# ESP32.net
KiCad netlist of a schematic drawn in Altium Designer
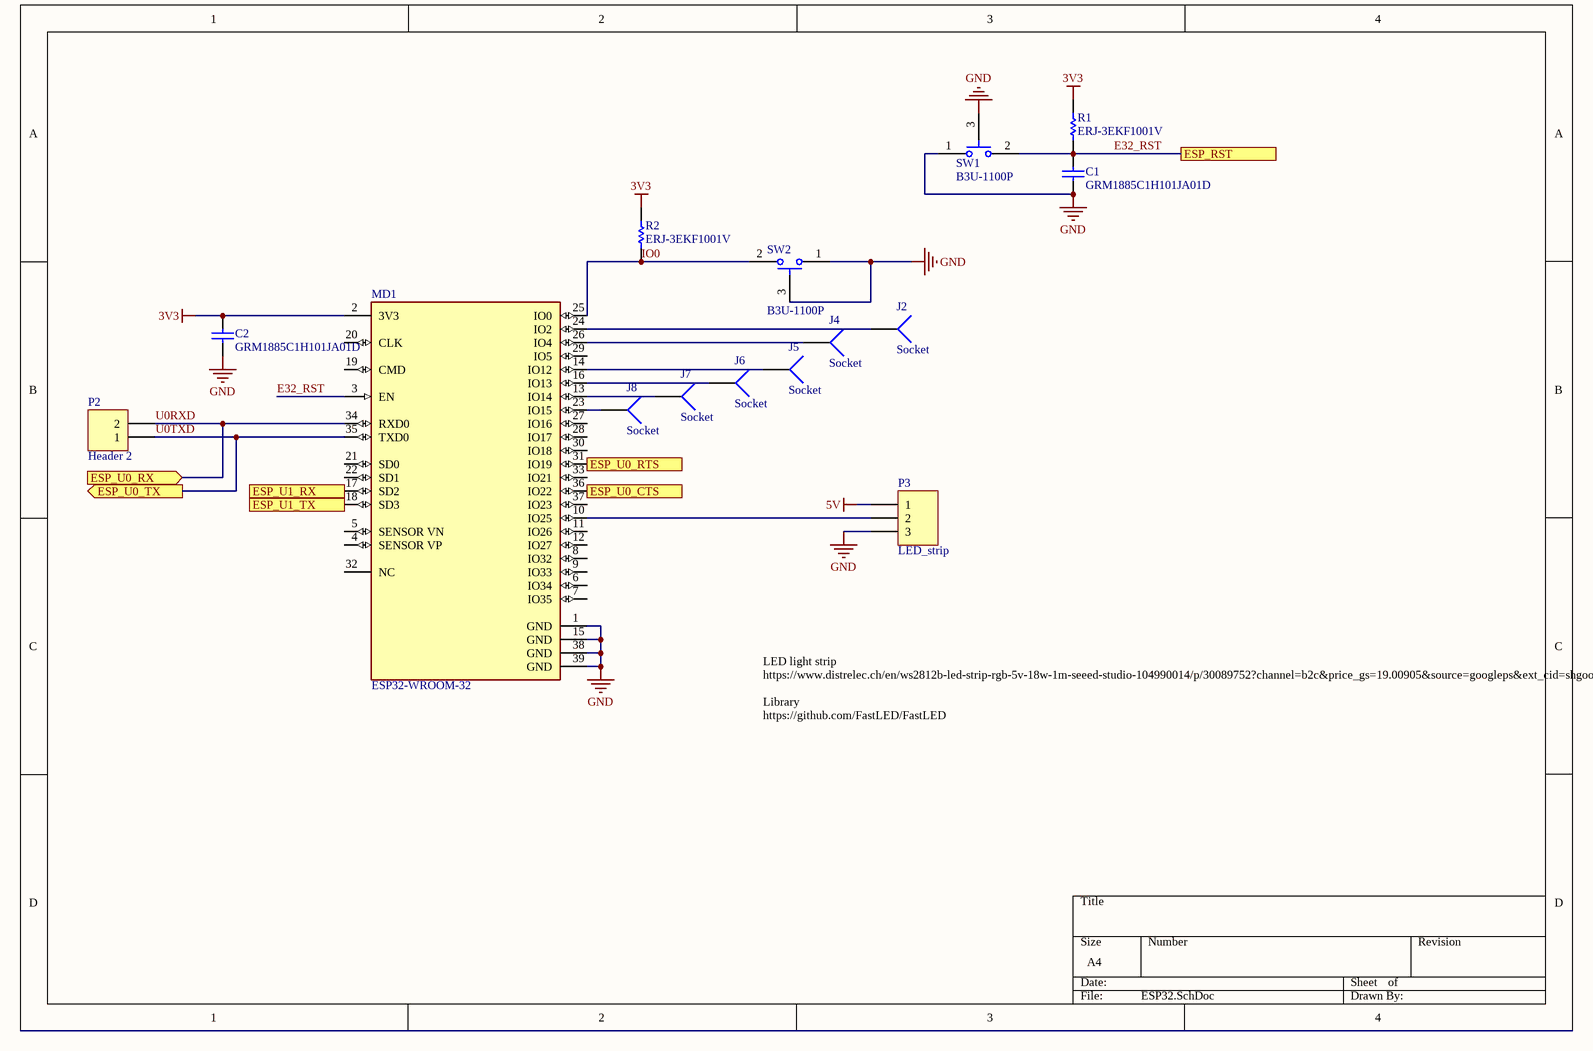
[diagram p0: ESP32.SchDoc]

(export (version "E")
  (design (tool "Eeschema 10.0.6"))
  (components
    (comp (ref "C1")
      (value "GRM1885C1H101JA01D")
      (footprint "CAPC1608X90X35ML10T15")
      (fields (field (name "MANUFACTURER") "Murata"))
      (libsource (lib "Altium Content Vault") (part "CAP"))
    )
    (comp (ref "C2")
      (value "GRM1885C1H101JA01D")
      (footprint "CAPC1608X90X35ML10T15")
      (fields (field (name "MANUFACTURER") "Murata"))
      (libsource (lib "Altium Content Vault") (part "CAP"))
    )
    (comp (ref "J2")
      (value "Socket")
      (footprint "PIN1")
      (fields (field (name "PUBLISHER") "Altium Limited"))
      (libsource (lib "Miscellaneous Connectors") (part "Socket"))
    )
    (comp (ref "J4")
      (value "Socket")
      (footprint "PIN1")
      (fields (field (name "PUBLISHER") "Altium Limited"))
      (libsource (lib "Miscellaneous Connectors") (part "Socket"))
    )
    (comp (ref "J5")
      (value "Socket")
      (footprint "PIN1")
      (fields (field (name "PUBLISHER") "Altium Limited"))
      (libsource (lib "Miscellaneous Connectors") (part "Socket"))
    )
    (comp (ref "J6")
      (value "Socket")
      (footprint "PIN1")
      (fields (field (name "PUBLISHER") "Altium Limited"))
      (libsource (lib "Miscellaneous Connectors") (part "Socket"))
    )
    (comp (ref "J7")
      (value "Socket")
      (footprint "PIN1")
      (fields (field (name "PUBLISHER") "Altium Limited"))
      (libsource (lib "Miscellaneous Connectors") (part "Socket"))
    )
    (comp (ref "J8")
      (value "Socket")
      (footprint "PIN1")
      (fields (field (name "PUBLISHER") "Altium Limited"))
      (libsource (lib "Miscellaneous Connectors") (part "Socket"))
    )
    (comp (ref "MD1")
      (value "ESP32-WROOM-32")
      (footprint "FP-ESP32-WROOM-32-MFG")
      (description "RX TXRX MOD WIFI SURFACE MOUNT")
      (libsource (lib "Altium Content Vault") (part "ee866abf0b6c51247b7f5cdebf2f250"))
    )
    (comp (ref "P2")
      (value "Header 2")
      (footprint "HDR1X2")
      (description "Header, 2-Pin")
      (fields (field (name "PUBLISHER") "Altium Limited"))
      (libsource (lib "Miscellaneous Connectors") (part "Header 2"))
    )
    (comp (ref "P3")
      (value "LED_strip")
      (footprint "HDR1X3")
      (description "Header, 3-Pin")
      (fields (field (name "PUBLISHER") "Altium Limited"))
      (libsource (lib "Miscellaneous Connectors") (part "Header 3"))
    )
    (comp (ref "R1")
      (value "ERJ-3EKF1001V")
      (footprint "RESC1608X55X30ML15T15")
      (fields (field (name "MANUFACTURER") "Panasonic"))
      (libsource (lib "Altium Content Vault") (part "RES"))
    )
    (comp (ref "R2")
      (value "ERJ-3EKF1001V")
      (footprint "RESC1608X55X30ML15T15")
      (fields (field (name "MANUFACTURER") "Panasonic"))
      (libsource (lib "Altium Content Vault") (part "RES"))
    )
    (comp (ref "SW1")
      (value "B3U-1100P")
      (footprint "FP-B3U-1100P-MFG")
      (description "SWITCH TACTILE SPST-NO 0.05A 12V")
      (libsource (lib "Altium Content Vault") (part "7997d68e903f5bf27f0182c444d3d80"))
    )
    (comp (ref "SW2")
      (value "B3U-1100P")
      (footprint "FP-B3U-1100P-MFG")
      (description "SWITCH TACTILE SPST-NO 0.05A 12V")
      (libsource (lib "Altium Content Vault") (part "7997d68e903f5bf27f0182c444d3d80"))
    )
  )
  (nets
    (net (code "1") (name "/E32_RST") (class "Default")
      (node (ref "C1") (pin "2") (pinfunction "2_2") (pintype "passive"))
      (node (ref "MD1") (pin "3") (pinfunction "EN_3") (pintype "input"))
      (node (ref "R1") (pin "1") (pinfunction "1_1") (pintype "passive"))
      (node (ref "SW1") (pin "2") (pinfunction "2_2") (pintype "passive"))
    )
    (net (code "2") (name "/ESP_U0_CTS") (class "Default")
      (node (ref "MD1") (pin "36") (pinfunction "IO22_36") (pintype "bidirectional"))
    )
    (net (code "3") (name "/ESP_U0_RTS") (class "Default")
      (node (ref "MD1") (pin "31") (pinfunction "IO19_31") (pintype "bidirectional"))
    )
    (net (code "4") (name "/ESP_U1_RX") (class "Default")
      (node (ref "MD1") (pin "17") (pinfunction "SD2_17") (pintype "bidirectional"))
    )
    (net (code "5") (name "/ESP_U1_TX") (class "Default")
      (node (ref "MD1") (pin "18") (pinfunction "SD3_18") (pintype "bidirectional"))
    )
    (net (code "6") (name "/IO0") (class "Default")
      (node (ref "MD1") (pin "25") (pinfunction "IO0_25") (pintype "bidirectional"))
      (node (ref "R2") (pin "1") (pinfunction "1_1") (pintype "passive"))
      (node (ref "SW2") (pin "2") (pinfunction "2_2") (pintype "passive"))
    )
    (net (code "7") (name "/U0RXD") (class "Default")
      (node (ref "MD1") (pin "34") (pinfunction "RXD0_34") (pintype "bidirectional"))
      (node (ref "P2") (pin "2") (pinfunction "2_2") (pintype "passive"))
    )
    (net (code "8") (name "/U0TXD") (class "Default")
      (node (ref "MD1") (pin "35") (pinfunction "TXD0_35") (pintype "bidirectional"))
      (node (ref "P2") (pin "1") (pinfunction "1_1") (pintype "passive"))
    )
    (net (code "9") (name "3V3") (class "Default")
      (node (ref "C2") (pin "2") (pinfunction "2_2") (pintype "passive"))
      (node (ref "MD1") (pin "2") (pinfunction "3V3_2") (pintype "power_in"))
      (node (ref "R1") (pin "2") (pinfunction "2_2") (pintype "passive"))
      (node (ref "R2") (pin "2") (pinfunction "2_2") (pintype "passive"))
    )
    (net (code "10") (name "5V") (class "Default")
      (node (ref "P3") (pin "1") (pinfunction "1_1") (pintype "passive"))
    )
    (net (code "11") (name "GND") (class "Default")
      (node (ref "C1") (pin "1") (pinfunction "1_1") (pintype "passive"))
      (node (ref "C2") (pin "1") (pinfunction "1_1") (pintype "passive"))
      (node (ref "MD1") (pin "1") (pinfunction "GND_1") (pintype "power_in"))
      (node (ref "MD1") (pin "15") (pinfunction "GND_15") (pintype "power_in"))
      (node (ref "MD1") (pin "38") (pinfunction "GND_38") (pintype "power_in"))
      (node (ref "MD1") (pin "39") (pinfunction "GND_39") (pintype "power_in"))
      (node (ref "P3") (pin "3") (pinfunction "3_3") (pintype "passive"))
      (node (ref "SW1") (pin "1") (pinfunction "1_1") (pintype "passive"))
      (node (ref "SW1") (pin "3") (pinfunction "3_3") (pintype "passive"))
      (node (ref "SW2") (pin "1") (pinfunction "1_1") (pintype "passive"))
      (node (ref "SW2") (pin "3") (pinfunction "3_3") (pintype "passive"))
    )
    (net (code "12") (name "Net-(MD1-IO2)") (class "Default")
      (node (ref "J2") (pin "1") (pinfunction "1_1") (pintype "passive"))
      (node (ref "MD1") (pin "24") (pinfunction "IO2_24") (pintype "bidirectional"))
    )
    (net (code "13") (name "Net-(MD1-IO4)") (class "Default")
      (node (ref "J4") (pin "1") (pinfunction "1_1") (pintype "passive"))
      (node (ref "MD1") (pin "26") (pinfunction "IO4_26") (pintype "bidirectional"))
    )
    (net (code "14") (name "Net-(MD1-IO12)") (class "Default")
      (node (ref "J5") (pin "1") (pinfunction "1_1") (pintype "passive"))
      (node (ref "MD1") (pin "14") (pinfunction "IO12_14") (pintype "bidirectional"))
    )
    (net (code "15") (name "Net-(MD1-IO13)") (class "Default")
      (node (ref "J6") (pin "1") (pinfunction "1_1") (pintype "passive"))
      (node (ref "MD1") (pin "16") (pinfunction "IO13_16") (pintype "bidirectional"))
    )
    (net (code "16") (name "Net-(MD1-IO14)") (class "Default")
      (node (ref "J7") (pin "1") (pinfunction "1_1") (pintype "passive"))
      (node (ref "MD1") (pin "13") (pinfunction "IO14_13") (pintype "bidirectional"))
    )
    (net (code "17") (name "Net-(MD1-IO15)") (class "Default")
      (node (ref "J8") (pin "1") (pinfunction "1_1") (pintype "passive"))
      (node (ref "MD1") (pin "23") (pinfunction "IO15_23") (pintype "bidirectional"))
    )
    (net (code "18") (name "Net-(MD1-IO25)") (class "Default")
      (node (ref "MD1") (pin "10") (pinfunction "IO25_10") (pintype "bidirectional"))
      (node (ref "P3") (pin "2") (pinfunction "2_2") (pintype "passive"))
    )
    (net (code "19") (name "unconnected-(MD1-CLK-Pad20)") (class "Default")
      (node (ref "MD1") (pin "20") (pinfunction "CLK_20") (pintype "bidirectional"))
    )
    (net (code "20") (name "unconnected-(MD1-CMD-Pad19)") (class "Default")
      (node (ref "MD1") (pin "19") (pinfunction "CMD_19") (pintype "bidirectional"))
    )
    (net (code "21") (name "unconnected-(MD1-IO5-Pad29)") (class "Default")
      (node (ref "MD1") (pin "29") (pinfunction "IO5_29") (pintype "bidirectional"))
    )
    (net (code "22") (name "unconnected-(MD1-IO16-Pad27)") (class "Default")
      (node (ref "MD1") (pin "27") (pinfunction "IO16_27") (pintype "bidirectional"))
    )
    (net (code "23") (name "unconnected-(MD1-IO17-Pad28)") (class "Default")
      (node (ref "MD1") (pin "28") (pinfunction "IO17_28") (pintype "bidirectional"))
    )
    (net (code "24") (name "unconnected-(MD1-IO18-Pad30)") (class "Default")
      (node (ref "MD1") (pin "30") (pinfunction "IO18_30") (pintype "bidirectional"))
    )
    (net (code "25") (name "unconnected-(MD1-IO21-Pad33)") (class "Default")
      (node (ref "MD1") (pin "33") (pinfunction "IO21_33") (pintype "bidirectional"))
    )
    (net (code "26") (name "unconnected-(MD1-IO23-Pad37)") (class "Default")
      (node (ref "MD1") (pin "37") (pinfunction "IO23_37") (pintype "bidirectional"))
    )
    (net (code "27") (name "unconnected-(MD1-IO26-Pad11)") (class "Default")
      (node (ref "MD1") (pin "11") (pinfunction "IO26_11") (pintype "bidirectional"))
    )
    (net (code "28") (name "unconnected-(MD1-IO27-Pad12)") (class "Default")
      (node (ref "MD1") (pin "12") (pinfunction "IO27_12") (pintype "bidirectional"))
    )
    (net (code "29") (name "unconnected-(MD1-IO32-Pad8)") (class "Default")
      (node (ref "MD1") (pin "8") (pinfunction "IO32_8") (pintype "bidirectional"))
    )
    (net (code "30") (name "unconnected-(MD1-IO33-Pad9)") (class "Default")
      (node (ref "MD1") (pin "9") (pinfunction "IO33_9") (pintype "bidirectional"))
    )
    (net (code "31") (name "unconnected-(MD1-IO34-Pad6)") (class "Default")
      (node (ref "MD1") (pin "6") (pinfunction "IO34_6") (pintype "bidirectional"))
    )
    (net (code "32") (name "unconnected-(MD1-IO35-Pad7)") (class "Default")
      (node (ref "MD1") (pin "7") (pinfunction "IO35_7") (pintype "bidirectional"))
    )
    (net (code "33") (name "unconnected-(MD1-NC-Pad32)") (class "Default")
      (node (ref "MD1") (pin "32") (pinfunction "NC_32") (pintype "passive"))
    )
    (net (code "34") (name "unconnected-(MD1-SD0-Pad21)") (class "Default")
      (node (ref "MD1") (pin "21") (pinfunction "SD0_21") (pintype "bidirectional"))
    )
    (net (code "35") (name "unconnected-(MD1-SD1-Pad22)") (class "Default")
      (node (ref "MD1") (pin "22") (pinfunction "SD1_22") (pintype "bidirectional"))
    )
    (net (code "36") (name "unconnected-(MD1-SENSOR_VN-Pad5)") (class "Default")
      (node (ref "MD1") (pin "5") (pinfunction "SENSOR_VN_5") (pintype "bidirectional"))
    )
    (net (code "37") (name "unconnected-(MD1-SENSOR_VP-Pad4)") (class "Default")
      (node (ref "MD1") (pin "4") (pinfunction "SENSOR_VP_4") (pintype "bidirectional"))
    )
  )
)
